# IOTM-222B.net
KiCad netlist of a schematic drawn in Altium Designer
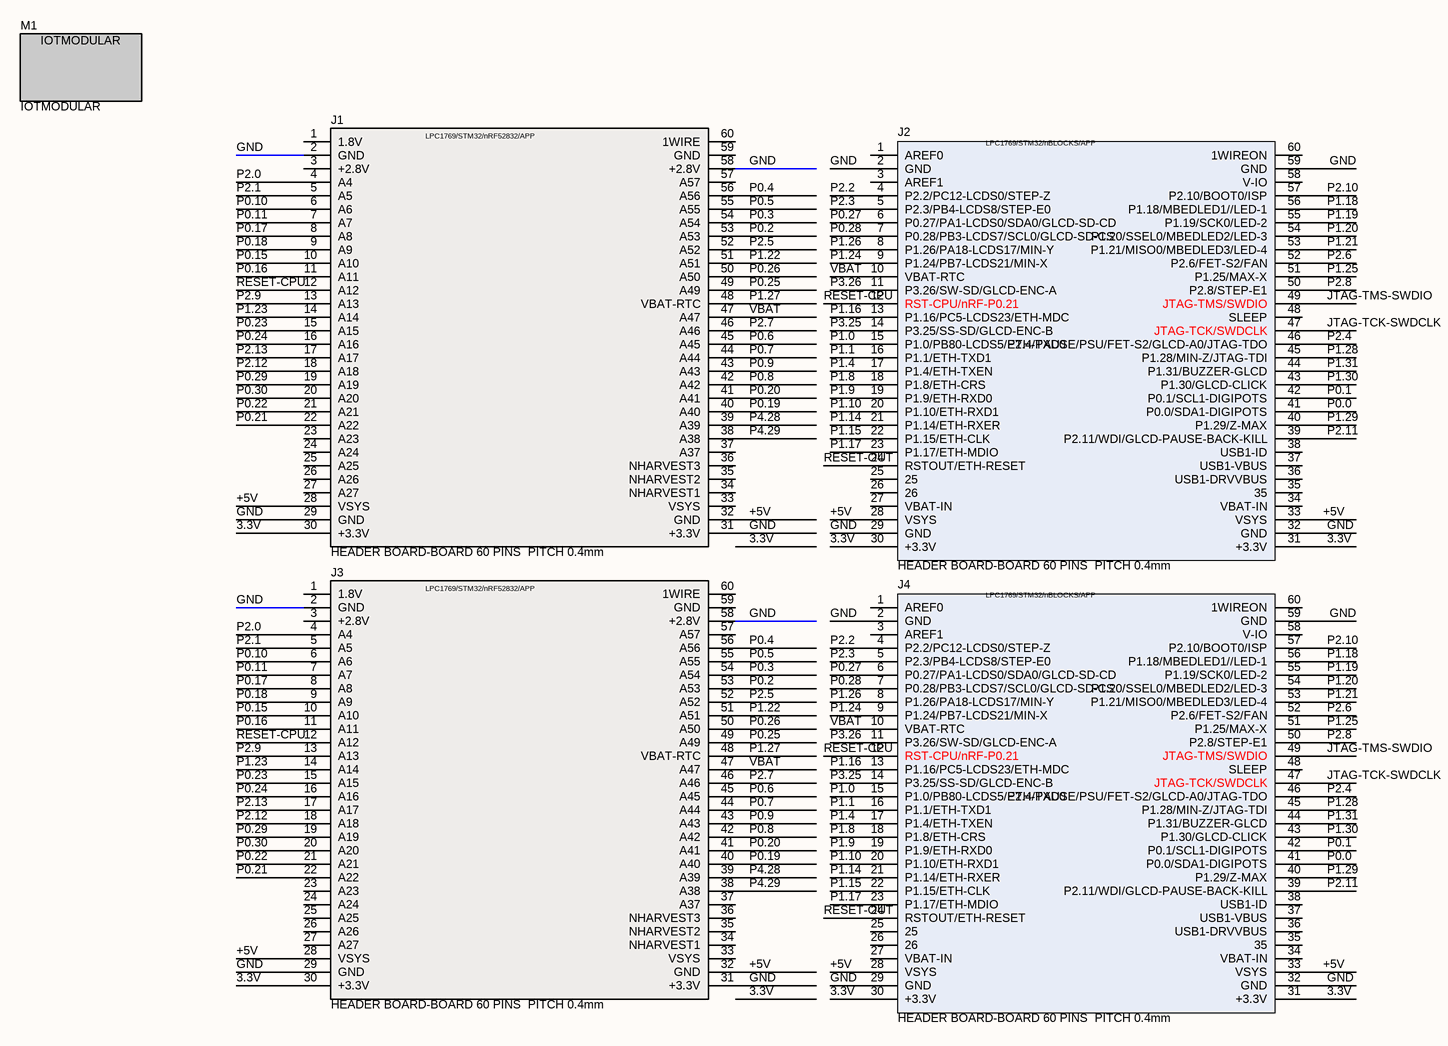
[diagram p0: IOTM-222B.SchDoc]

(export (version "E")
  (design (tool "Eeschema 10.0.6"))
  (components
    (comp (ref "J1")
      (value "HEADER BOARD-BOARD 60 PINS  PITCH 0.4mm")
      (footprint "IOT-HIROSE-FX6-60S-0.8SV(71)-TOP")
      (libsource (lib "NX1") (part "HEADER 60-NBUS-A"))
    )
    (comp (ref "J2")
      (value "HEADER BOARD-BOARD 60 PINS  PITCH 0.4mm")
      (footprint "IOT-HIROSE-FX6-60P-0.8SV(71)-TOP")
      (libsource (lib "NX1") (part "HEADER 60-NBUS-B"))
    )
    (comp (ref "J3")
      (value "HEADER BOARD-BOARD 60 PINS  PITCH 0.4mm")
      (footprint "IOT-HIROSE-FX6-60P-0.8SV(71)-TOP")
      (libsource (lib "NX1") (part "HEADER 60-NBUS-A"))
    )
    (comp (ref "J4")
      (value "HEADER BOARD-BOARD 60 PINS  PITCH 0.4mm")
      (footprint "IOT-HIROSE-FX6-60S-0.8SV(71)-TOP")
      (libsource (lib "NX1") (part "HEADER 60-NBUS-B"))
    )
    (comp (ref "M1")
      (value "IOTMODULAR")
      (footprint "IOTMODULAR")
      (libsource (lib "NX1") (part "IOTMODULAR"))
    )
  )
  (nets
    (net (code "1") (name "/+5V") (class "Default")
      (node (ref "J1") (pin "28") (pinfunction "VSYS_28") (pintype "passive"))
      (node (ref "J1") (pin "32") (pinfunction "GND_32") (pintype "passive"))
      (node (ref "J2") (pin "28") (pinfunction "VSYS_28") (pintype "passive"))
      (node (ref "J2") (pin "33") (pinfunction "VSYS_33") (pintype "passive"))
      (node (ref "J3") (pin "28") (pinfunction "VSYS_28") (pintype "passive"))
      (node (ref "J3") (pin "32") (pinfunction "GND_32") (pintype "passive"))
      (node (ref "J4") (pin "28") (pinfunction "VSYS_28") (pintype "passive"))
      (node (ref "J4") (pin "33") (pinfunction "VSYS_33") (pintype "passive"))
    )
    (net (code "2") (name "/3.3V") (class "Default")
      (node (ref "J1") (pin "30") (pinfunction "+3.3V_30") (pintype "passive"))
      (node (ref "J2") (pin "30") (pinfunction "+3.3V_30") (pintype "passive"))
      (node (ref "J2") (pin "31") (pinfunction "+3.3V_31") (pintype "passive"))
      (node (ref "J3") (pin "30") (pinfunction "+3.3V_30") (pintype "passive"))
      (node (ref "J4") (pin "30") (pinfunction "+3.3V_30") (pintype "passive"))
      (node (ref "J4") (pin "31") (pinfunction "+3.3V_31") (pintype "passive"))
    )
    (net (code "3") (name "/GND") (class "Default")
      (node (ref "J1") (pin "2") (pinfunction "GND_2") (pintype "passive"))
      (node (ref "J1") (pin "29") (pinfunction "GND_29") (pintype "passive"))
      (node (ref "J1") (pin "31") (pinfunction "+3.3V_31") (pintype "passive"))
      (node (ref "J1") (pin "58") (pinfunction "+2.8V_58") (pintype "passive"))
      (node (ref "J2") (pin "2") (pinfunction "GND_2") (pintype "passive"))
      (node (ref "J2") (pin "29") (pinfunction "GND_29") (pintype "passive"))
      (node (ref "J2") (pin "32") (pinfunction "GND_32") (pintype "passive"))
      (node (ref "J2") (pin "59") (pinfunction "GND_59") (pintype "passive"))
      (node (ref "J3") (pin "2") (pinfunction "GND_2") (pintype "passive"))
      (node (ref "J3") (pin "29") (pinfunction "GND_29") (pintype "passive"))
      (node (ref "J3") (pin "31") (pinfunction "+3.3V_31") (pintype "passive"))
      (node (ref "J3") (pin "58") (pinfunction "+2.8V_58") (pintype "passive"))
      (node (ref "J4") (pin "2") (pinfunction "GND_2") (pintype "passive"))
      (node (ref "J4") (pin "29") (pinfunction "GND_29") (pintype "passive"))
      (node (ref "J4") (pin "32") (pinfunction "GND_32") (pintype "passive"))
      (node (ref "J4") (pin "59") (pinfunction "GND_59") (pintype "passive"))
    )
    (net (code "4") (name "/JTAG-TCK-SWDCLK") (class "Default")
      (node (ref "J2") (pin "47") (pinfunction "JTAG-TCK/SWDCLK_47") (pintype "passive"))
      (node (ref "J4") (pin "47") (pinfunction "JTAG-TCK/SWDCLK_47") (pintype "passive"))
    )
    (net (code "5") (name "/JTAG-TMS-SWDIO") (class "Default")
      (node (ref "J2") (pin "49") (pinfunction "JTAG-TMS/SWDIO_49") (pintype "passive"))
      (node (ref "J4") (pin "49") (pinfunction "JTAG-TMS/SWDIO_49") (pintype "passive"))
    )
    (net (code "6") (name "/P0.0") (class "Default")
      (node (ref "J2") (pin "41") (pinfunction "P0.0/SDA1-DIGIPOTS_41") (pintype "passive"))
      (node (ref "J4") (pin "41") (pinfunction "P0.0/SDA1-DIGIPOTS_41") (pintype "passive"))
    )
    (net (code "7") (name "/P0.1") (class "Default")
      (node (ref "J2") (pin "42") (pinfunction "P0.1/SCL1-DIGIPOTS_42") (pintype "passive"))
      (node (ref "J4") (pin "42") (pinfunction "P0.1/SCL1-DIGIPOTS_42") (pintype "passive"))
    )
    (net (code "8") (name "/P0.2") (class "Default")
      (node (ref "J1") (pin "53") (pinfunction "A53_53") (pintype "passive"))
      (node (ref "J3") (pin "53") (pinfunction "A53_53") (pintype "passive"))
    )
    (net (code "9") (name "/P0.3") (class "Default")
      (node (ref "J1") (pin "54") (pinfunction "A54_54") (pintype "passive"))
      (node (ref "J3") (pin "54") (pinfunction "A54_54") (pintype "passive"))
    )
    (net (code "10") (name "/P0.4") (class "Default")
      (node (ref "J1") (pin "56") (pinfunction "A56_56") (pintype "passive"))
      (node (ref "J3") (pin "56") (pinfunction "A56_56") (pintype "passive"))
    )
    (net (code "11") (name "/P0.5") (class "Default")
      (node (ref "J1") (pin "55") (pinfunction "A55_55") (pintype "passive"))
      (node (ref "J3") (pin "55") (pinfunction "A55_55") (pintype "passive"))
    )
    (net (code "12") (name "/P0.6") (class "Default")
      (node (ref "J1") (pin "45") (pinfunction "A45_45") (pintype "passive"))
      (node (ref "J3") (pin "45") (pinfunction "A45_45") (pintype "passive"))
    )
    (net (code "13") (name "/P0.7") (class "Default")
      (node (ref "J1") (pin "44") (pinfunction "A44_44") (pintype "passive"))
      (node (ref "J3") (pin "44") (pinfunction "A44_44") (pintype "passive"))
    )
    (net (code "14") (name "/P0.8") (class "Default")
      (node (ref "J1") (pin "42") (pinfunction "A42_42") (pintype "passive"))
      (node (ref "J3") (pin "42") (pinfunction "A42_42") (pintype "passive"))
    )
    (net (code "15") (name "/P0.9") (class "Default")
      (node (ref "J1") (pin "43") (pinfunction "A43_43") (pintype "passive"))
      (node (ref "J3") (pin "43") (pinfunction "A43_43") (pintype "passive"))
    )
    (net (code "16") (name "/P0.10") (class "Default")
      (node (ref "J1") (pin "6") (pinfunction "A6_6") (pintype "passive"))
      (node (ref "J3") (pin "6") (pinfunction "A6_6") (pintype "passive"))
    )
    (net (code "17") (name "/P0.11") (class "Default")
      (node (ref "J1") (pin "7") (pinfunction "A7_7") (pintype "passive"))
      (node (ref "J3") (pin "7") (pinfunction "A7_7") (pintype "passive"))
    )
    (net (code "18") (name "/P0.15") (class "Default")
      (node (ref "J1") (pin "10") (pinfunction "A10_10") (pintype "passive"))
      (node (ref "J3") (pin "10") (pinfunction "A10_10") (pintype "passive"))
    )
    (net (code "19") (name "/P0.16") (class "Default")
      (node (ref "J1") (pin "11") (pinfunction "A11_11") (pintype "passive"))
      (node (ref "J3") (pin "11") (pinfunction "A11_11") (pintype "passive"))
    )
    (net (code "20") (name "/P0.17") (class "Default")
      (node (ref "J1") (pin "8") (pinfunction "A8_8") (pintype "passive"))
      (node (ref "J3") (pin "8") (pinfunction "A8_8") (pintype "passive"))
    )
    (net (code "21") (name "/P0.18") (class "Default")
      (node (ref "J1") (pin "9") (pinfunction "A9_9") (pintype "passive"))
      (node (ref "J3") (pin "9") (pinfunction "A9_9") (pintype "passive"))
    )
    (net (code "22") (name "/P0.19") (class "Default")
      (node (ref "J1") (pin "40") (pinfunction "A40_40") (pintype "passive"))
      (node (ref "J3") (pin "40") (pinfunction "A40_40") (pintype "passive"))
    )
    (net (code "23") (name "/P0.20") (class "Default")
      (node (ref "J1") (pin "41") (pinfunction "A41_41") (pintype "passive"))
      (node (ref "J3") (pin "41") (pinfunction "A41_41") (pintype "passive"))
    )
    (net (code "24") (name "/P0.21") (class "Default")
      (node (ref "J1") (pin "22") (pinfunction "A22_22") (pintype "passive"))
      (node (ref "J3") (pin "22") (pinfunction "A22_22") (pintype "passive"))
    )
    (net (code "25") (name "/P0.22") (class "Default")
      (node (ref "J1") (pin "21") (pinfunction "A21_21") (pintype "passive"))
      (node (ref "J3") (pin "21") (pinfunction "A21_21") (pintype "passive"))
    )
    (net (code "26") (name "/P0.23") (class "Default")
      (node (ref "J1") (pin "15") (pinfunction "A15_15") (pintype "passive"))
      (node (ref "J3") (pin "15") (pinfunction "A15_15") (pintype "passive"))
    )
    (net (code "27") (name "/P0.24") (class "Default")
      (node (ref "J1") (pin "16") (pinfunction "A16_16") (pintype "passive"))
      (node (ref "J3") (pin "16") (pinfunction "A16_16") (pintype "passive"))
    )
    (net (code "28") (name "/P0.25") (class "Default")
      (node (ref "J1") (pin "49") (pinfunction "A49_49") (pintype "passive"))
      (node (ref "J3") (pin "49") (pinfunction "A49_49") (pintype "passive"))
    )
    (net (code "29") (name "/P0.26") (class "Default")
      (node (ref "J1") (pin "50") (pinfunction "A50_50") (pintype "passive"))
      (node (ref "J3") (pin "50") (pinfunction "A50_50") (pintype "passive"))
    )
    (net (code "30") (name "/P0.27") (class "Default")
      (node (ref "J2") (pin "6") (pinfunction "P0.27/PA1-LCDS0/SDA0/GLCD-SD-CD_6") (pintype "passive"))
      (node (ref "J4") (pin "6") (pinfunction "P0.27/PA1-LCDS0/SDA0/GLCD-SD-CD_6") (pintype "passive"))
    )
    (net (code "31") (name "/P0.28") (class "Default")
      (node (ref "J2") (pin "7") (pinfunction "P0.28/PB3-LCDS7/SCL0/GLCD-SD-CS_7") (pintype "passive"))
      (node (ref "J4") (pin "7") (pinfunction "P0.28/PB3-LCDS7/SCL0/GLCD-SD-CS_7") (pintype "passive"))
    )
    (net (code "32") (name "/P0.29") (class "Default")
      (node (ref "J1") (pin "19") (pinfunction "A19_19") (pintype "passive"))
      (node (ref "J3") (pin "19") (pinfunction "A19_19") (pintype "passive"))
    )
    (net (code "33") (name "/P0.30") (class "Default")
      (node (ref "J1") (pin "20") (pinfunction "A20_20") (pintype "passive"))
      (node (ref "J3") (pin "20") (pinfunction "A20_20") (pintype "passive"))
    )
    (net (code "34") (name "/P1.0") (class "Default")
      (node (ref "J2") (pin "15") (pinfunction "P1.0/PB80-LCDS5/ETH-TXD0_15") (pintype "passive"))
      (node (ref "J4") (pin "15") (pinfunction "P1.0/PB80-LCDS5/ETH-TXD0_15") (pintype "passive"))
    )
    (net (code "35") (name "/P1.1") (class "Default")
      (node (ref "J2") (pin "16") (pinfunction "P1.1/ETH-TXD1_16") (pintype "passive"))
      (node (ref "J4") (pin "16") (pinfunction "P1.1/ETH-TXD1_16") (pintype "passive"))
    )
    (net (code "36") (name "/P1.4") (class "Default")
      (node (ref "J2") (pin "17") (pinfunction "P1.4/ETH-TXEN_17") (pintype "passive"))
      (node (ref "J4") (pin "17") (pinfunction "P1.4/ETH-TXEN_17") (pintype "passive"))
    )
    (net (code "37") (name "/P1.8") (class "Default")
      (node (ref "J2") (pin "18") (pinfunction "P1.8/ETH-CRS_18") (pintype "passive"))
      (node (ref "J4") (pin "18") (pinfunction "P1.8/ETH-CRS_18") (pintype "passive"))
    )
    (net (code "38") (name "/P1.9") (class "Default")
      (node (ref "J2") (pin "19") (pinfunction "P1.9/ETH-RXD0_19") (pintype "passive"))
      (node (ref "J4") (pin "19") (pinfunction "P1.9/ETH-RXD0_19") (pintype "passive"))
    )
    (net (code "39") (name "/P1.10") (class "Default")
      (node (ref "J2") (pin "20") (pinfunction "P1.10/ETH-RXD1_20") (pintype "passive"))
      (node (ref "J4") (pin "20") (pinfunction "P1.10/ETH-RXD1_20") (pintype "passive"))
    )
    (net (code "40") (name "/P1.14") (class "Default")
      (node (ref "J2") (pin "21") (pinfunction "P1.14/ETH-RXER_21") (pintype "passive"))
      (node (ref "J4") (pin "21") (pinfunction "P1.14/ETH-RXER_21") (pintype "passive"))
    )
    (net (code "41") (name "/P1.15") (class "Default")
      (node (ref "J2") (pin "22") (pinfunction "P1.15/ETH-CLK_22") (pintype "passive"))
      (node (ref "J4") (pin "22") (pinfunction "P1.15/ETH-CLK_22") (pintype "passive"))
    )
    (net (code "42") (name "/P1.16") (class "Default")
      (node (ref "J2") (pin "13") (pinfunction "P1.16/PC5-LCDS23/ETH-MDC_13") (pintype "passive"))
      (node (ref "J4") (pin "13") (pinfunction "P1.16/PC5-LCDS23/ETH-MDC_13") (pintype "passive"))
    )
    (net (code "43") (name "/P1.17") (class "Default")
      (node (ref "J2") (pin "23") (pinfunction "P1.17/ETH-MDIO_23") (pintype "passive"))
      (node (ref "J4") (pin "23") (pinfunction "P1.17/ETH-MDIO_23") (pintype "passive"))
    )
    (net (code "44") (name "/P1.18") (class "Default")
      (node (ref "J2") (pin "56") (pinfunction "P1.18/MBEDLED1//LED-1_56") (pintype "passive"))
      (node (ref "J4") (pin "56") (pinfunction "P1.18/MBEDLED1//LED-1_56") (pintype "passive"))
    )
    (net (code "45") (name "/P1.19") (class "Default")
      (node (ref "J2") (pin "55") (pinfunction "P1.19/SCK0/LED-2_55") (pintype "passive"))
      (node (ref "J4") (pin "55") (pinfunction "P1.19/SCK0/LED-2_55") (pintype "passive"))
    )
    (net (code "46") (name "/P1.20") (class "Default")
      (node (ref "J2") (pin "54") (pinfunction "P1.20/SSEL0/MBEDLED2/LED-3_54") (pintype "passive"))
      (node (ref "J4") (pin "54") (pinfunction "P1.20/SSEL0/MBEDLED2/LED-3_54") (pintype "passive"))
    )
    (net (code "47") (name "/P1.21") (class "Default")
      (node (ref "J2") (pin "53") (pinfunction "P1.21/MISO0/MBEDLED3/LED-4_53") (pintype "passive"))
      (node (ref "J4") (pin "53") (pinfunction "P1.21/MISO0/MBEDLED3/LED-4_53") (pintype "passive"))
    )
    (net (code "48") (name "/P1.22") (class "Default")
      (node (ref "J1") (pin "51") (pinfunction "A51_51") (pintype "passive"))
      (node (ref "J3") (pin "51") (pinfunction "A51_51") (pintype "passive"))
    )
    (net (code "49") (name "/P1.23") (class "Default")
      (node (ref "J1") (pin "14") (pinfunction "A14_14") (pintype "passive"))
      (node (ref "J3") (pin "14") (pinfunction "A14_14") (pintype "passive"))
    )
    (net (code "50") (name "/P1.24") (class "Default")
      (node (ref "J2") (pin "9") (pinfunction "P1.24/PB7-LCDS21/MIN-X_9") (pintype "passive"))
      (node (ref "J4") (pin "9") (pinfunction "P1.24/PB7-LCDS21/MIN-X_9") (pintype "passive"))
    )
    (net (code "51") (name "/P1.25") (class "Default")
      (node (ref "J2") (pin "51") (pinfunction "P1.25/MAX-X_51") (pintype "passive"))
      (node (ref "J4") (pin "51") (pinfunction "P1.25/MAX-X_51") (pintype "passive"))
    )
    (net (code "52") (name "/P1.26") (class "Default")
      (node (ref "J2") (pin "8") (pinfunction "P1.26/PA18-LCDS17/MIN-Y_8") (pintype "passive"))
      (node (ref "J4") (pin "8") (pinfunction "P1.26/PA18-LCDS17/MIN-Y_8") (pintype "passive"))
    )
    (net (code "53") (name "/P1.27") (class "Default")
      (node (ref "J1") (pin "48") (pinfunction "VBAT-RTC_48") (pintype "passive"))
      (node (ref "J3") (pin "48") (pinfunction "VBAT-RTC_48") (pintype "passive"))
    )
    (net (code "54") (name "/P1.28") (class "Default")
      (node (ref "J2") (pin "45") (pinfunction "P1.28/MIN-Z/JTAG-TDI_45") (pintype "passive"))
      (node (ref "J4") (pin "45") (pinfunction "P1.28/MIN-Z/JTAG-TDI_45") (pintype "passive"))
    )
    (net (code "55") (name "/P1.29") (class "Default")
      (node (ref "J2") (pin "40") (pinfunction "P1.29/Z-MAX_40") (pintype "passive"))
      (node (ref "J4") (pin "40") (pinfunction "P1.29/Z-MAX_40") (pintype "passive"))
    )
    (net (code "56") (name "/P1.30") (class "Default")
      (node (ref "J2") (pin "43") (pinfunction "P1.30/GLCD-CLICK_43") (pintype "passive"))
      (node (ref "J4") (pin "43") (pinfunction "P1.30/GLCD-CLICK_43") (pintype "passive"))
    )
    (net (code "57") (name "/P1.31") (class "Default")
      (node (ref "J2") (pin "44") (pinfunction "P1.31/BUZZER-GLCD_44") (pintype "passive"))
      (node (ref "J4") (pin "44") (pinfunction "P1.31/BUZZER-GLCD_44") (pintype "passive"))
    )
    (net (code "58") (name "/P2.0") (class "Default")
      (node (ref "J1") (pin "4") (pinfunction "A4_4") (pintype "passive"))
      (node (ref "J3") (pin "4") (pinfunction "A4_4") (pintype "passive"))
    )
    (net (code "59") (name "/P2.1") (class "Default")
      (node (ref "J1") (pin "5") (pinfunction "A5_5") (pintype "passive"))
      (node (ref "J3") (pin "5") (pinfunction "A5_5") (pintype "passive"))
    )
    (net (code "60") (name "/P2.2") (class "Default")
      (node (ref "J2") (pin "4") (pinfunction "P2.2/PC12-LCDS0/STEP-Z_4") (pintype "passive"))
      (node (ref "J4") (pin "4") (pinfunction "P2.2/PC12-LCDS0/STEP-Z_4") (pintype "passive"))
    )
    (net (code "61") (name "/P2.3") (class "Default")
      (node (ref "J2") (pin "5") (pinfunction "P2.3/PB4-LCDS8/STEP-E0_5") (pintype "passive"))
      (node (ref "J4") (pin "5") (pinfunction "P2.3/PB4-LCDS8/STEP-E0_5") (pintype "passive"))
    )
    (net (code "62") (name "/P2.4") (class "Default")
      (node (ref "J2") (pin "46") (pinfunction "P2.4/PAUSE/PSU/FET-S2/GLCD-A0/JTAG-TDO_46") (pintype "passive"))
      (node (ref "J4") (pin "46") (pinfunction "P2.4/PAUSE/PSU/FET-S2/GLCD-A0/JTAG-TDO_46") (pintype "passive"))
    )
    (net (code "63") (name "/P2.5") (class "Default")
      (node (ref "J1") (pin "52") (pinfunction "A52_52") (pintype "passive"))
      (node (ref "J3") (pin "52") (pinfunction "A52_52") (pintype "passive"))
    )
    (net (code "64") (name "/P2.6") (class "Default")
      (node (ref "J2") (pin "52") (pinfunction "P2.6/FET-S2/FAN_52") (pintype "passive"))
      (node (ref "J4") (pin "52") (pinfunction "P2.6/FET-S2/FAN_52") (pintype "passive"))
    )
    (net (code "65") (name "/P2.7") (class "Default")
      (node (ref "J1") (pin "46") (pinfunction "A46_46") (pintype "passive"))
      (node (ref "J3") (pin "46") (pinfunction "A46_46") (pintype "passive"))
    )
    (net (code "66") (name "/P2.8") (class "Default")
      (node (ref "J2") (pin "50") (pinfunction "P2.8/STEP-E1_50") (pintype "passive"))
      (node (ref "J4") (pin "50") (pinfunction "P2.8/STEP-E1_50") (pintype "passive"))
    )
    (net (code "67") (name "/P2.9") (class "Default")
      (node (ref "J1") (pin "13") (pinfunction "A13_13") (pintype "passive"))
      (node (ref "J3") (pin "13") (pinfunction "A13_13") (pintype "passive"))
    )
    (net (code "68") (name "/P2.10") (class "Default")
      (node (ref "J2") (pin "57") (pinfunction "P2.10/BOOT0/ISP_57") (pintype "passive"))
      (node (ref "J4") (pin "57") (pinfunction "P2.10/BOOT0/ISP_57") (pintype "passive"))
    )
    (net (code "69") (name "/P2.11") (class "Default")
      (node (ref "J2") (pin "39") (pinfunction "P2.11/WDI/GLCD-PAUSE-BACK-KILL_39") (pintype "passive"))
      (node (ref "J4") (pin "39") (pinfunction "P2.11/WDI/GLCD-PAUSE-BACK-KILL_39") (pintype "passive"))
    )
    (net (code "70") (name "/P2.12") (class "Default")
      (node (ref "J1") (pin "18") (pinfunction "A18_18") (pintype "passive"))
      (node (ref "J3") (pin "18") (pinfunction "A18_18") (pintype "passive"))
    )
    (net (code "71") (name "/P2.13") (class "Default")
      (node (ref "J1") (pin "17") (pinfunction "A17_17") (pintype "passive"))
      (node (ref "J3") (pin "17") (pinfunction "A17_17") (pintype "passive"))
    )
    (net (code "72") (name "/P3.25") (class "Default")
      (node (ref "J2") (pin "14") (pinfunction "P3.25/SS-SD/GLCD-ENC-B_14") (pintype "passive"))
      (node (ref "J4") (pin "14") (pinfunction "P3.25/SS-SD/GLCD-ENC-B_14") (pintype "passive"))
    )
    (net (code "73") (name "/P3.26") (class "Default")
      (node (ref "J2") (pin "11") (pinfunction "P3.26/SW-SD/GLCD-ENC-A_11") (pintype "passive"))
      (node (ref "J4") (pin "11") (pinfunction "P3.26/SW-SD/GLCD-ENC-A_11") (pintype "passive"))
    )
    (net (code "74") (name "/P4.28") (class "Default")
      (node (ref "J1") (pin "39") (pinfunction "A39_39") (pintype "passive"))
      (node (ref "J3") (pin "39") (pinfunction "A39_39") (pintype "passive"))
    )
    (net (code "75") (name "/P4.29") (class "Default")
      (node (ref "J1") (pin "38") (pinfunction "A38_38") (pintype "passive"))
      (node (ref "J3") (pin "38") (pinfunction "A38_38") (pintype "passive"))
    )
    (net (code "76") (name "/RESET-CPU") (class "Default")
      (node (ref "J1") (pin "12") (pinfunction "A12_12") (pintype "passive"))
      (node (ref "J2") (pin "12") (pinfunction "RST-CPU/nRF-P0.21_12") (pintype "passive"))
      (node (ref "J3") (pin "12") (pinfunction "A12_12") (pintype "passive"))
      (node (ref "J4") (pin "12") (pinfunction "RST-CPU/nRF-P0.21_12") (pintype "passive"))
    )
    (net (code "77") (name "/RESET-OUT") (class "Default")
      (node (ref "J2") (pin "24") (pinfunction "RSTOUT/ETH-RESET_24") (pintype "passive"))
      (node (ref "J4") (pin "24") (pinfunction "RSTOUT/ETH-RESET_24") (pintype "passive"))
    )
    (net (code "78") (name "/VBAT") (class "Default")
      (node (ref "J1") (pin "47") (pinfunction "A47_47") (pintype "passive"))
      (node (ref "J2") (pin "10") (pinfunction "VBAT-RTC_10") (pintype "passive"))
      (node (ref "J3") (pin "47") (pinfunction "A47_47") (pintype "passive"))
      (node (ref "J4") (pin "10") (pinfunction "VBAT-RTC_10") (pintype "passive"))
    )
    (net (code "79") (name "unconnected-(J1-+2.8V-Pad3)") (class "Default")
      (node (ref "J1") (pin "3") (pinfunction "+2.8V_3") (pintype "passive"))
    )
    (net (code "80") (name "unconnected-(J1-1.8V-Pad1)") (class "Default")
      (node (ref "J1") (pin "1") (pinfunction "1.8V_1") (pintype "passive"))
    )
    (net (code "81") (name "unconnected-(J1-1WIRE-Pad60)") (class "Default")
      (node (ref "J1") (pin "60") (pinfunction "1WIRE_60") (pintype "passive"))
    )
    (net (code "82") (name "unconnected-(J1-A23-Pad23)") (class "Default")
      (node (ref "J1") (pin "23") (pinfunction "A23_23") (pintype "passive"))
    )
    (net (code "83") (name "unconnected-(J1-A24-Pad24)") (class "Default")
      (node (ref "J1") (pin "24") (pinfunction "A24_24") (pintype "passive"))
    )
    (net (code "84") (name "unconnected-(J1-A25-Pad25)") (class "Default")
      (node (ref "J1") (pin "25") (pinfunction "A25_25") (pintype "passive"))
    )
    (net (code "85") (name "unconnected-(J1-A26-Pad26)") (class "Default")
      (node (ref "J1") (pin "26") (pinfunction "A26_26") (pintype "passive"))
    )
    (net (code "86") (name "unconnected-(J1-A27-Pad27)") (class "Default")
      (node (ref "J1") (pin "27") (pinfunction "A27_27") (pintype "passive"))
    )
    (net (code "87") (name "unconnected-(J1-A37-Pad37)") (class "Default")
      (node (ref "J1") (pin "37") (pinfunction "A37_37") (pintype "passive"))
    )
    (net (code "88") (name "unconnected-(J1-A57-Pad57)") (class "Default")
      (node (ref "J1") (pin "57") (pinfunction "A57_57") (pintype "passive"))
    )
    (net (code "89") (name "unconnected-(J1-GND-Pad59)") (class "Default")
      (node (ref "J1") (pin "59") (pinfunction "GND_59") (pintype "passive"))
    )
    (net (code "90") (name "unconnected-(J1-NHARVEST1-Pad34)") (class "Default")
      (node (ref "J1") (pin "34") (pinfunction "NHARVEST1_34") (pintype "passive"))
    )
    (net (code "91") (name "unconnected-(J1-NHARVEST2-Pad35)") (class "Default")
      (node (ref "J1") (pin "35") (pinfunction "NHARVEST2_35") (pintype "passive"))
    )
    (net (code "92") (name "unconnected-(J1-NHARVEST3-Pad36)") (class "Default")
      (node (ref "J1") (pin "36") (pinfunction "NHARVEST3_36") (pintype "passive"))
    )
    (net (code "93") (name "unconnected-(J1-VSYS-Pad33)") (class "Default")
      (node (ref "J1") (pin "33") (pinfunction "VSYS_33") (pintype "passive"))
    )
    (net (code "94") (name "unconnected-(J2-1WIREON-Pad60)") (class "Default")
      (node (ref "J2") (pin "60") (pinfunction "1WIREON_60") (pintype "passive"))
    )
    (net (code "95") (name "unconnected-(J2-AREF0-Pad1)") (class "Default")
      (node (ref "J2") (pin "1") (pinfunction "AREF0_1") (pintype "passive"))
    )
    (net (code "96") (name "unconnected-(J2-AREF1-Pad3)") (class "Default")
      (node (ref "J2") (pin "3") (pinfunction "AREF1_3") (pintype "passive"))
    )
    (net (code "97") (name "unconnected-(J2-Pad25)") (class "Default")
      (node (ref "J2") (pin "25") (pinfunction "25_25") (pintype "passive"))
    )
    (net (code "98") (name "unconnected-(J2-Pad26)") (class "Default")
      (node (ref "J2") (pin "26") (pinfunction "26_26") (pintype "passive"))
    )
    (net (code "99") (name "unconnected-(J2-Pad35)") (class "Default")
      (node (ref "J2") (pin "35") (pinfunction "35_35") (pintype "passive"))
    )
    (net (code "100") (name "unconnected-(J2-SLEEP-Pad48)") (class "Default")
      (node (ref "J2") (pin "48") (pinfunction "SLEEP_48") (pintype "passive"))
    )
    (net (code "101") (name "unconnected-(J2-USB1-DRVVBUS-Pad36)") (class "Default")
      (node (ref "J2") (pin "36") (pinfunction "USB1-DRVVBUS_36") (pintype "passive"))
    )
    (net (code "102") (name "unconnected-(J2-USB1-ID-Pad38)") (class "Default")
      (node (ref "J2") (pin "38") (pinfunction "USB1-ID_38") (pintype "passive"))
    )
    (net (code "103") (name "unconnected-(J2-USB1-VBUS-Pad37)") (class "Default")
      (node (ref "J2") (pin "37") (pinfunction "USB1-VBUS_37") (pintype "passive"))
    )
    (net (code "104") (name "unconnected-(J2-V-IO-Pad58)") (class "Default")
      (node (ref "J2") (pin "58") (pinfunction "V-IO_58") (pintype "passive"))
    )
    (net (code "105") (name "unconnected-(J2-VBAT-IN-Pad27)") (class "Default")
      (node (ref "J2") (pin "27") (pinfunction "VBAT-IN_27") (pintype "passive"))
    )
    (net (code "106") (name "unconnected-(J2-VBAT-IN-Pad34)") (class "Default")
      (node (ref "J2") (pin "34") (pinfunction "VBAT-IN_34") (pintype "passive"))
    )
    (net (code "107") (name "unconnected-(J3-+2.8V-Pad3)") (class "Default")
      (node (ref "J3") (pin "3") (pinfunction "+2.8V_3") (pintype "passive"))
    )
    (net (code "108") (name "unconnected-(J3-1.8V-Pad1)") (class "Default")
      (node (ref "J3") (pin "1") (pinfunction "1.8V_1") (pintype "passive"))
    )
    (net (code "109") (name "unconnected-(J3-1WIRE-Pad60)") (class "Default")
      (node (ref "J3") (pin "60") (pinfunction "1WIRE_60") (pintype "passive"))
    )
    (net (code "110") (name "unconnected-(J3-A23-Pad23)") (class "Default")
      (node (ref "J3") (pin "23") (pinfunction "A23_23") (pintype "passive"))
    )
    (net (code "111") (name "unconnected-(J3-A24-Pad24)") (class "Default")
      (node (ref "J3") (pin "24") (pinfunction "A24_24") (pintype "passive"))
    )
    (net (code "112") (name "unconnected-(J3-A25-Pad25)") (class "Default")
      (node (ref "J3") (pin "25") (pinfunction "A25_25") (pintype "passive"))
    )
    (net (code "113") (name "unconnected-(J3-A26-Pad26)") (class "Default")
      (node (ref "J3") (pin "26") (pinfunction "A26_26") (pintype "passive"))
    )
    (net (code "114") (name "unconnected-(J3-A27-Pad27)") (class "Default")
      (node (ref "J3") (pin "27") (pinfunction "A27_27") (pintype "passive"))
    )
    (net (code "115") (name "unconnected-(J3-A37-Pad37)") (class "Default")
      (node (ref "J3") (pin "37") (pinfunction "A37_37") (pintype "passive"))
    )
    (net (code "116") (name "unconnected-(J3-A57-Pad57)") (class "Default")
      (node (ref "J3") (pin "57") (pinfunction "A57_57") (pintype "passive"))
    )
    (net (code "117") (name "unconnected-(J3-GND-Pad59)") (class "Default")
      (node (ref "J3") (pin "59") (pinfunction "GND_59") (pintype "passive"))
    )
    (net (code "118") (name "unconnected-(J3-NHARVEST1-Pad34)") (class "Default")
      (node (ref "J3") (pin "34") (pinfunction "NHARVEST1_34") (pintype "passive"))
    )
    (net (code "119") (name "unconnected-(J3-NHARVEST2-Pad35)") (class "Default")
      (node (ref "J3") (pin "35") (pinfunction "NHARVEST2_35") (pintype "passive"))
    )
    (net (code "120") (name "unconnected-(J3-NHARVEST3-Pad36)") (class "Default")
      (node (ref "J3") (pin "36") (pinfunction "NHARVEST3_36") (pintype "passive"))
    )
    (net (code "121") (name "unconnected-(J3-VSYS-Pad33)") (class "Default")
      (node (ref "J3") (pin "33") (pinfunction "VSYS_33") (pintype "passive"))
    )
    (net (code "122") (name "unconnected-(J4-1WIREON-Pad60)") (class "Default")
      (node (ref "J4") (pin "60") (pinfunction "1WIREON_60") (pintype "passive"))
    )
    (net (code "123") (name "unconnected-(J4-AREF0-Pad1)") (class "Default")
      (node (ref "J4") (pin "1") (pinfunction "AREF0_1") (pintype "passive"))
    )
    (net (code "124") (name "unconnected-(J4-AREF1-Pad3)") (class "Default")
      (node (ref "J4") (pin "3") (pinfunction "AREF1_3") (pintype "passive"))
    )
    (net (code "125") (name "unconnected-(J4-Pad25)") (class "Default")
      (node (ref "J4") (pin "25") (pinfunction "25_25") (pintype "passive"))
    )
    (net (code "126") (name "unconnected-(J4-Pad26)") (class "Default")
      (node (ref "J4") (pin "26") (pinfunction "26_26") (pintype "passive"))
    )
    (net (code "127") (name "unconnected-(J4-Pad35)") (class "Default")
      (node (ref "J4") (pin "35") (pinfunction "35_35") (pintype "passive"))
    )
    (net (code "128") (name "unconnected-(J4-SLEEP-Pad48)") (class "Default")
      (node (ref "J4") (pin "48") (pinfunction "SLEEP_48") (pintype "passive"))
    )
    (net (code "129") (name "unconnected-(J4-USB1-DRVVBUS-Pad36)") (class "Default")
      (node (ref "J4") (pin "36") (pinfunction "USB1-DRVVBUS_36") (pintype "passive"))
    )
    (net (code "130") (name "unconnected-(J4-USB1-ID-Pad38)") (class "Default")
      (node (ref "J4") (pin "38") (pinfunction "USB1-ID_38") (pintype "passive"))
    )
    (net (code "131") (name "unconnected-(J4-USB1-VBUS-Pad37)") (class "Default")
      (node (ref "J4") (pin "37") (pinfunction "USB1-VBUS_37") (pintype "passive"))
    )
    (net (code "132") (name "unconnected-(J4-V-IO-Pad58)") (class "Default")
      (node (ref "J4") (pin "58") (pinfunction "V-IO_58") (pintype "passive"))
    )
    (net (code "133") (name "unconnected-(J4-VBAT-IN-Pad27)") (class "Default")
      (node (ref "J4") (pin "27") (pinfunction "VBAT-IN_27") (pintype "passive"))
    )
    (net (code "134") (name "unconnected-(J4-VBAT-IN-Pad34)") (class "Default")
      (node (ref "J4") (pin "34") (pinfunction "VBAT-IN_34") (pintype "passive"))
    )
  )
)
